# Sheet1.net
KiCad netlist of a schematic drawn in Altium Designer
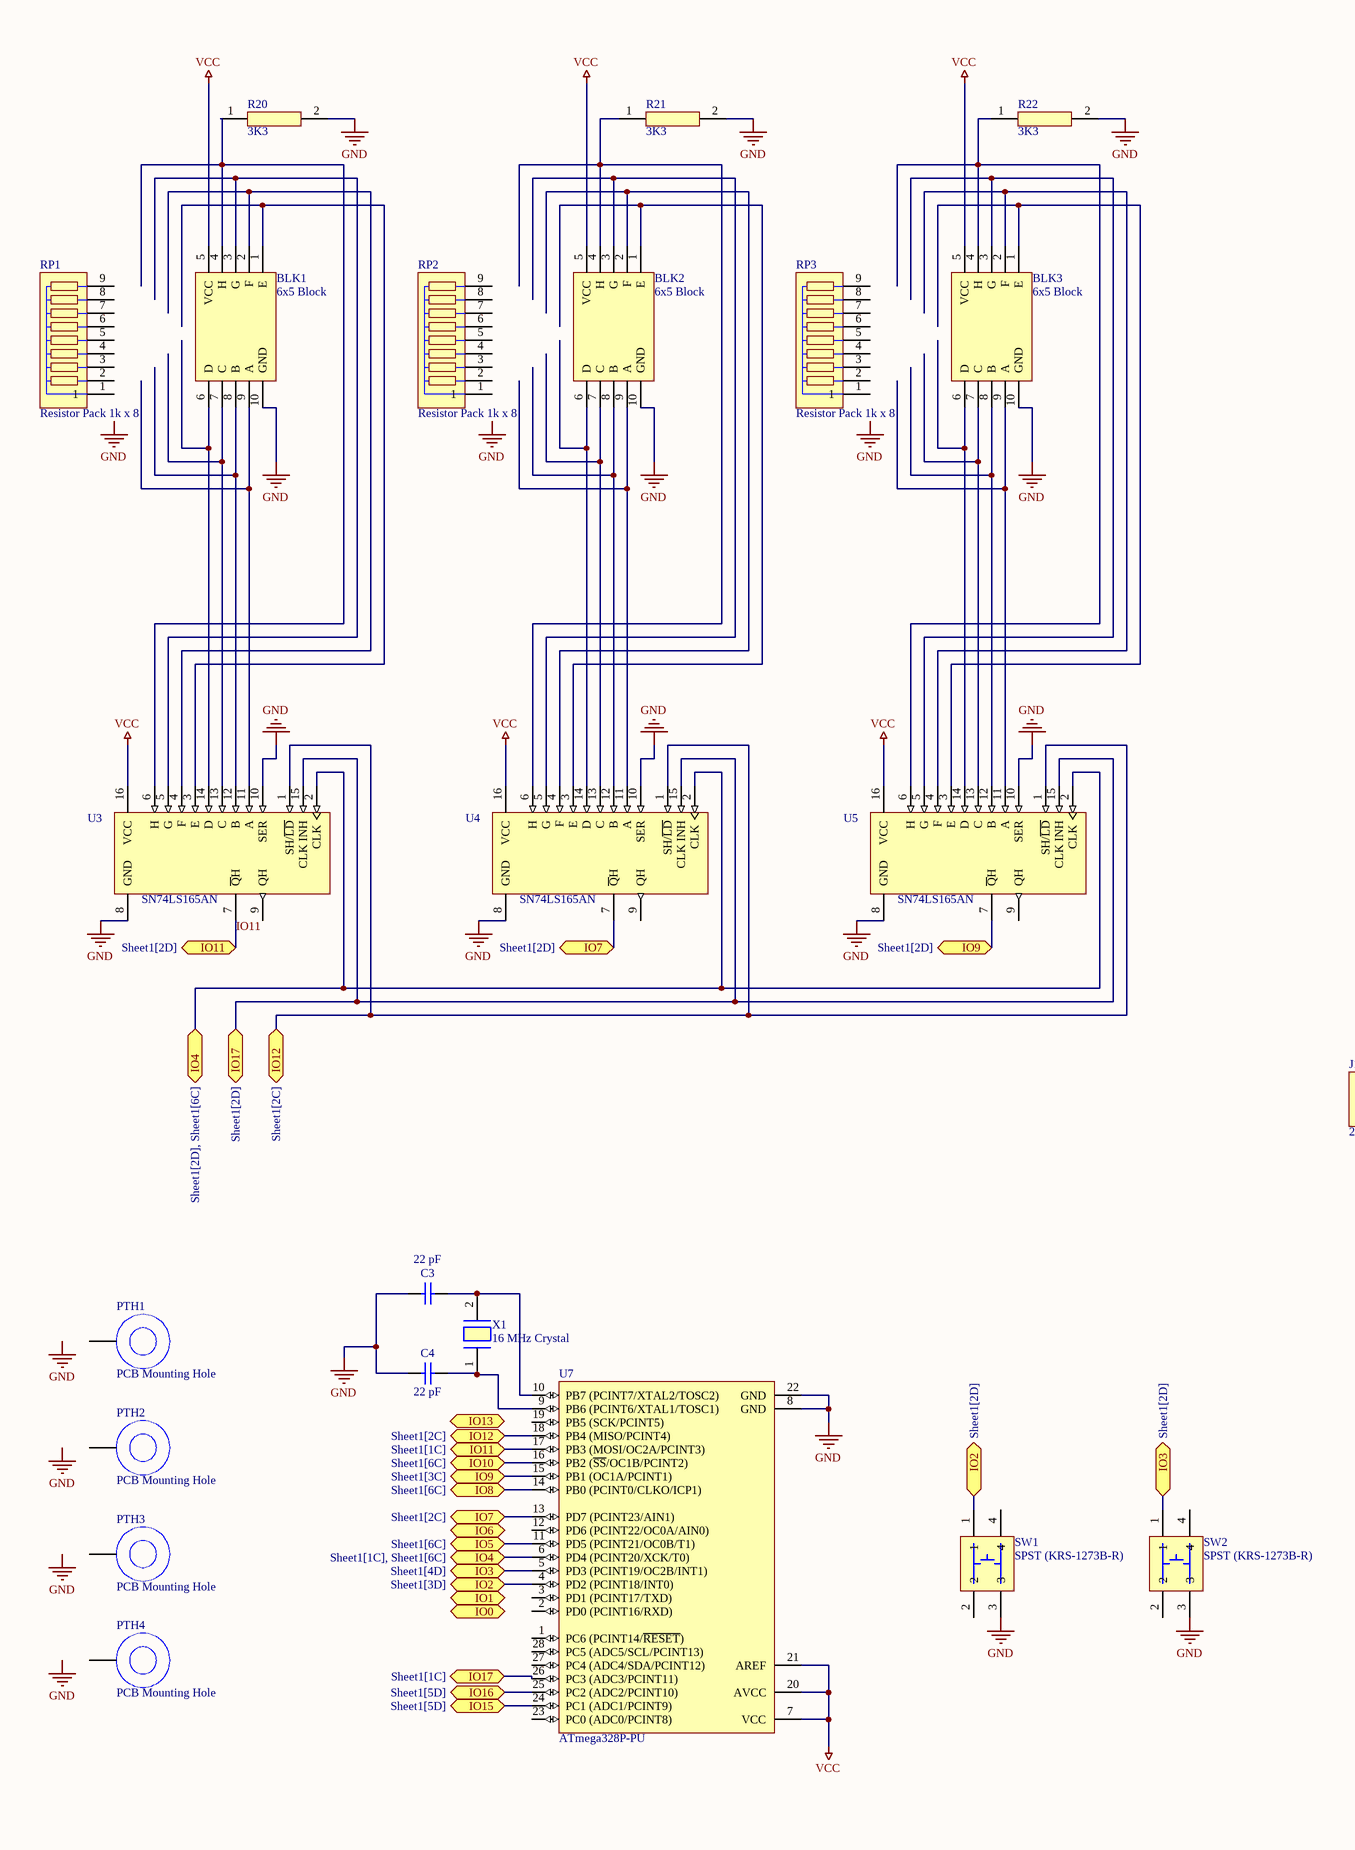
[diagram p0: Sheet1.SchDoc, left]
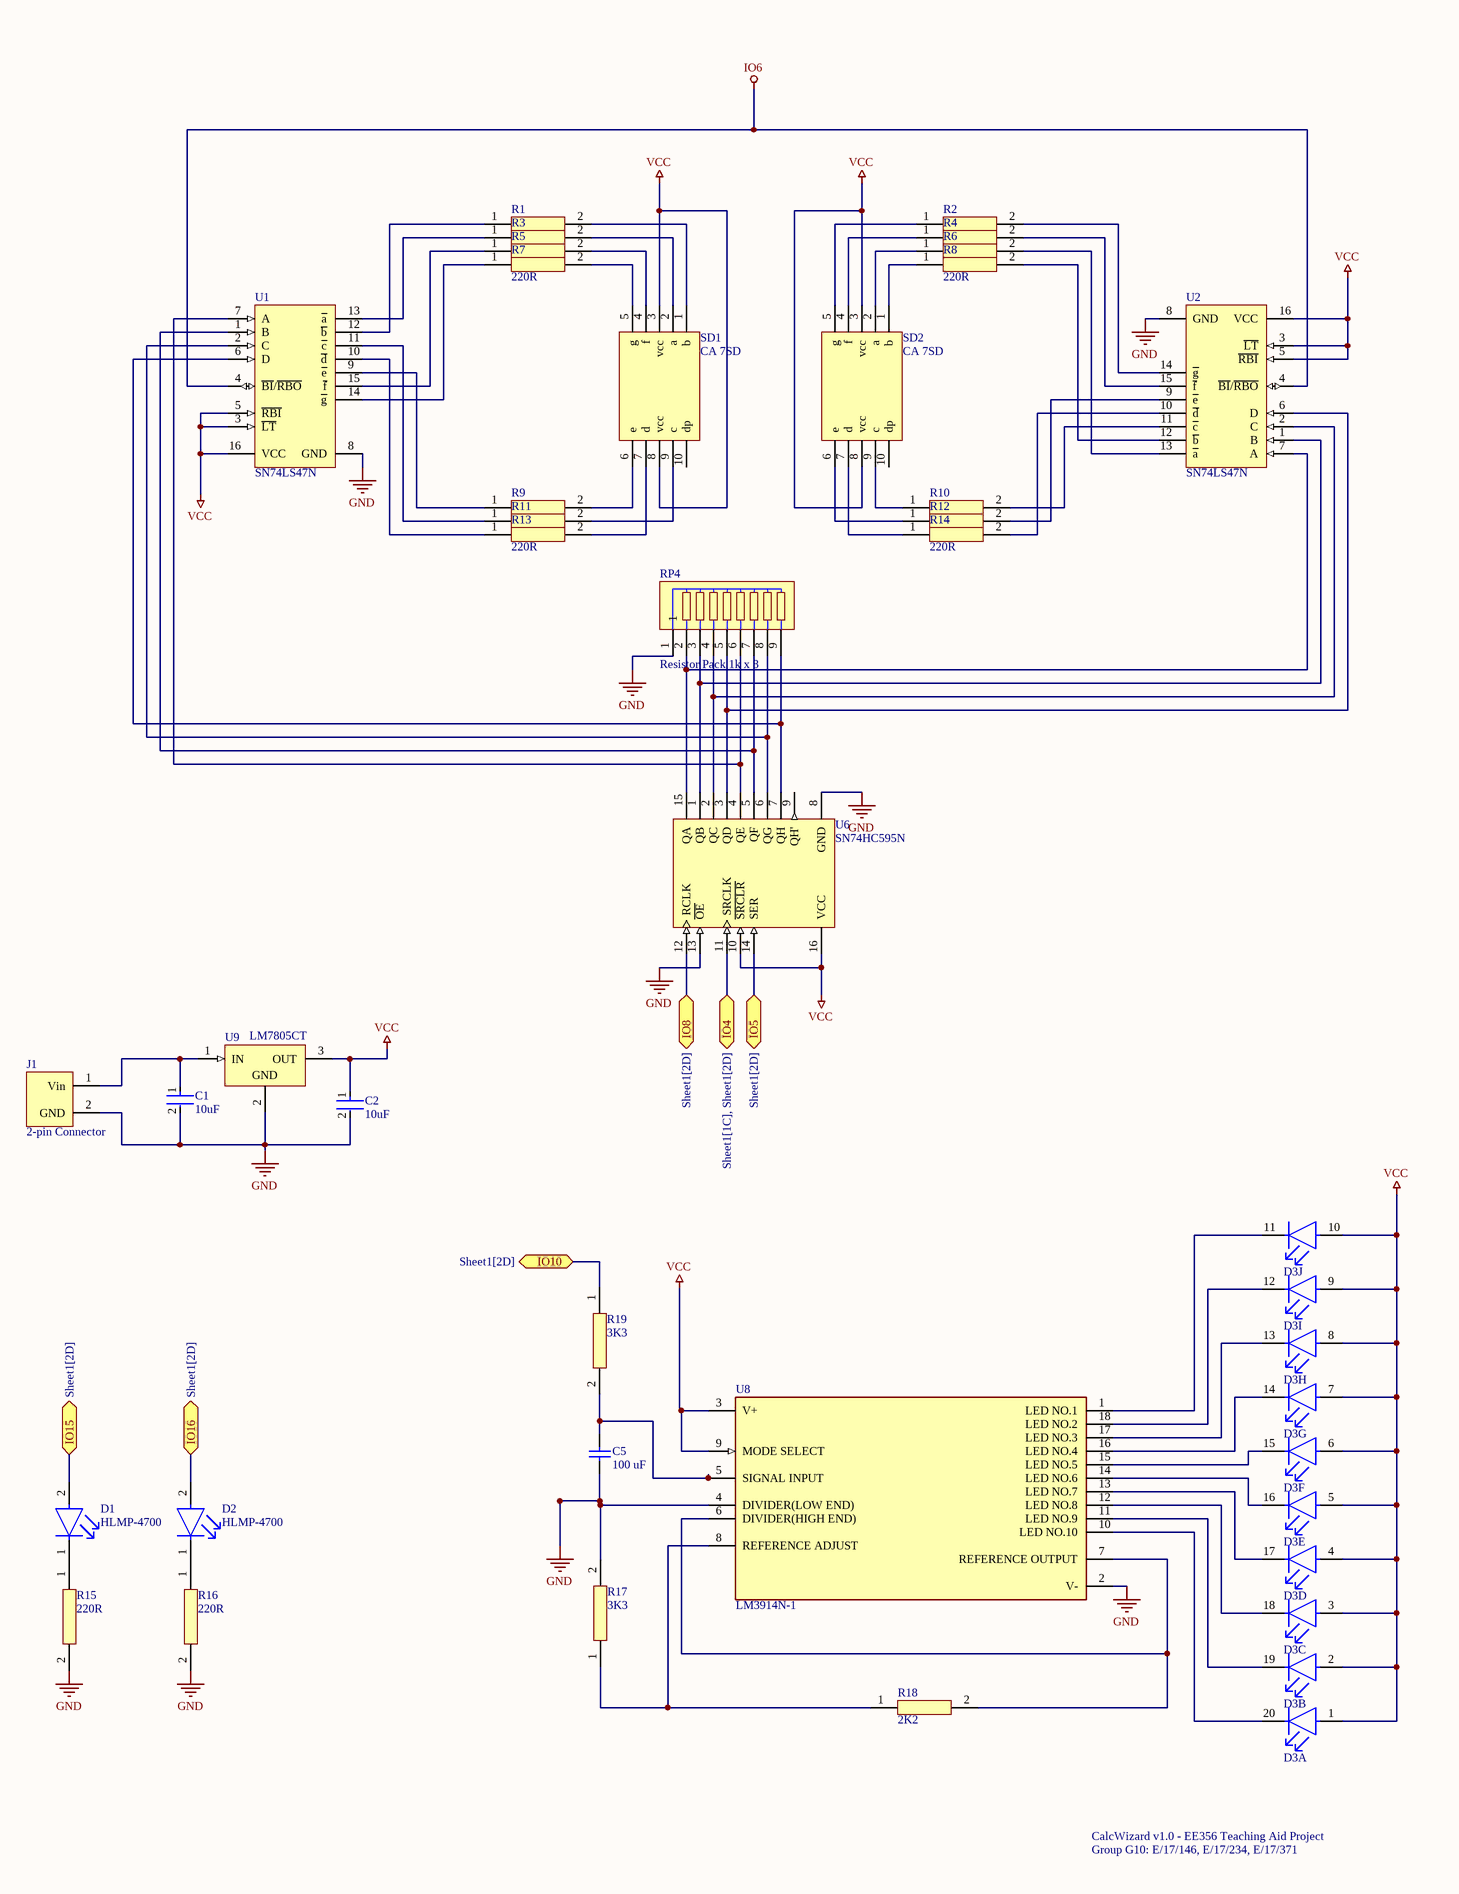
[diagram p1: Sheet1.SchDoc, right]

(export (version "E")
  (design (tool "Eeschema 10.0.6"))
  (components
    (comp (ref "BLK1")
      (value "6x5 Block")
      (footprint "Block_6x5")
      (libsource (lib "Schlib1") (part "Block_6x5"))
    )
    (comp (ref "BLK2")
      (value "6x5 Block")
      (footprint "Block_6x5")
      (libsource (lib "Schlib1") (part "Block_6x5"))
    )
    (comp (ref "BLK3")
      (value "6x5 Block")
      (footprint "Block_6x5")
      (libsource (lib "Schlib1") (part "Block_6x5"))
    )
    (comp (ref "C1")
      (value "10uF")
      (footprint "FP-RCE3DB-MFG")
      (description "Cap Ceramic 10uF 25V X7R ±10% Radial 2.5mm +125°C Automotive Bulk (RCER71E106K3A2H03B)")
      (fields (field (name "TOLERANCE") "10%"))
      (libsource (lib "Altium Content Vault") (part "b4654b650e69147ec39a6b967a45e02"))
    )
    (comp (ref "C2")
      (value "10uF")
      (footprint "FP-RCE3DB-MFG")
      (description "Cap Ceramic 10uF 25V X7R ±10% Radial 2.5mm +125°C Automotive Bulk (RCER71E106K3A2H03B)")
      (fields (field (name "TOLERANCE") "10%"))
      (libsource (lib "Altium Content Vault") (part "b4654b650e69147ec39a6b967a45e02"))
    )
    (comp (ref "C3")
      (value "22 pF")
      (footprint "KEMT-C315-THT-2")
      (description "Capacitor, Ceramic, 22 pF, +/-10 %, 100 V, -55 to 125 degC, 2-Pin THD, RoHS, Bulk")
      (libsource (lib "Altium Content Vault") (part "CAP-NP-2"))
    )
    (comp (ref "C4")
      (value "22 pF")
      (footprint "KEMT-C315-THT-2")
      (description "Capacitor, Ceramic, 22 pF, +/-10 %, 100 V, -55 to 125 degC, 2-Pin THD, RoHS, Bulk")
      (libsource (lib "Altium Content Vault") (part "CAP-NP-2"))
    )
    (comp (ref "C5")
      (value "100 uF")
      (footprint "KEMT-C315-THT-2")
      (description "Capacitor, Ceramic, 100 uF, +/-10 %, 100 V, -55 to 125 degC, 2-Pin THD, RoHS, Bulk")
      (libsource (lib "Altium Content Vault") (part "CAP-NP-2"))
    )
    (comp (ref "D1")
      (value "HLMP-4700")
      (footprint "FP-HLMP-4700-MFG")
      (description "LED RED DIFFUSED T-1 3/4 T/H")
      (fields
        (field (name "OCTOPART") "https://octopart.com/hlmp-4700-broadcom-71130526")
        (field (name "MANUFACTURER") "Broadcom")
      )
      (libsource (lib "Altium Content Vault") (part "8706943c75ba83719d021d2fdc84c58"))
    )
    (comp (ref "D2")
      (value "HLMP-4700")
      (footprint "FP-HLMP-4700-MFG")
      (description "LED RED DIFFUSED T-1 3/4 T/H")
      (fields
        (field (name "OCTOPART") "https://octopart.com/hlmp-4700-broadcom-71130526")
        (field (name "MANUFACTURER") "Broadcom")
      )
      (libsource (lib "Altium Content Vault") (part "8706943c75ba83719d021d2fdc84c58"))
    )
    (comp (ref "D3")
      (value "SSA-LXB10HW-GF/LP")
      (footprint "FP-SSA-LXB10HW-GF-LP-MFG")
      (description "LED ARRAY 10X25MM 10SEG RED DIFF")
      (fields
        (field (name "OCTOPART") "https://octopart.com/ssa-lxb10hw-gf%2Flp-lumex-548235")
        (field (name "MANUFACTURER") "lumex")
      )
      (libsource (lib "Altium Content Vault") (part "0ad3f8813297581e4dba16f0763b6c7"))
    )
    (comp (ref "J1")
      (value "2-pin Connector")
      (footprint "2-pin Connector")
      (description "Female, 2C, Straight, .100\"CC; 3.20mm Tail, No Mt. 100u\" Tin; PBT, Phos Bronze, 105 C")
      (fields
        (field (name "MANUFACTURER") "Sullins")
        (field (name "MANUFACTURER PART NUMBER") "PPTC021LFBN-RC")
      )
      (libsource (lib "Schlib1") (part "PPTC021LFBN-RC"))
    )
    (comp (ref "PTH1")
      (value "PCB Mounting Hole")
      (footprint "PTH 2mm")
      (libsource (lib "Schlib1") (part "PTH"))
    )
    (comp (ref "PTH2")
      (value "PCB Mounting Hole")
      (footprint "PTH 2mm")
      (libsource (lib "Schlib1") (part "PTH"))
    )
    (comp (ref "PTH3")
      (value "PCB Mounting Hole")
      (footprint "PTH 2mm")
      (libsource (lib "Schlib1") (part "PTH"))
    )
    (comp (ref "PTH4")
      (value "PCB Mounting Hole")
      (footprint "PTH 2mm")
      (libsource (lib "Schlib1") (part "PTH"))
    )
    (comp (ref "R1")
      (value "220R")
      (footprint "CFR_400mil")
      (description "General Type Carbon Film Resistor 220Ohm 1/4W 5% Axial Bulk")
      (fields
        (field (name "MANUFACTURER") "Yageo")
        (field (name "MANUFACTURER PART NUMBER") "CFR-25JB-52-220R")
      )
      (libsource (lib "Schlib1") (part "CFR-25JB-52-220R"))
    )
    (comp (ref "R2")
      (value "220R")
      (footprint "CFR_400mil")
      (description "General Type Carbon Film Resistor 220Ohm 1/4W 5% Axial Bulk")
      (fields
        (field (name "MANUFACTURER") "Yageo")
        (field (name "MANUFACTURER PART NUMBER") "CFR-25JB-52-220R")
      )
      (libsource (lib "Schlib1") (part "CFR-25JB-52-220R"))
    )
    (comp (ref "R3")
      (value "220R")
      (footprint "CFR_400mil")
      (description "General Type Carbon Film Resistor 220Ohm 1/4W 5% Axial Bulk")
      (fields
        (field (name "MANUFACTURER") "Yageo")
        (field (name "MANUFACTURER PART NUMBER") "CFR-25JB-52-220R")
      )
      (libsource (lib "Schlib1") (part "CFR-25JB-52-220R"))
    )
    (comp (ref "R4")
      (value "220R")
      (footprint "CFR_400mil")
      (description "General Type Carbon Film Resistor 220Ohm 1/4W 5% Axial Bulk")
      (fields
        (field (name "MANUFACTURER") "Yageo")
        (field (name "MANUFACTURER PART NUMBER") "CFR-25JB-52-220R")
      )
      (libsource (lib "Schlib1") (part "CFR-25JB-52-220R"))
    )
    (comp (ref "R5")
      (value "220R")
      (footprint "CFR_400mil")
      (description "General Type Carbon Film Resistor 220Ohm 1/4W 5% Axial Bulk")
      (fields
        (field (name "MANUFACTURER") "Yageo")
        (field (name "MANUFACTURER PART NUMBER") "CFR-25JB-52-220R")
      )
      (libsource (lib "Schlib1") (part "CFR-25JB-52-220R"))
    )
    (comp (ref "R6")
      (value "220R")
      (footprint "CFR_400mil")
      (description "General Type Carbon Film Resistor 220Ohm 1/4W 5% Axial Bulk")
      (fields
        (field (name "MANUFACTURER") "Yageo")
        (field (name "MANUFACTURER PART NUMBER") "CFR-25JB-52-220R")
      )
      (libsource (lib "Schlib1") (part "CFR-25JB-52-220R"))
    )
    (comp (ref "R7")
      (value "220R")
      (footprint "CFR_400mil")
      (description "General Type Carbon Film Resistor 220Ohm 1/4W 5% Axial Bulk")
      (fields
        (field (name "MANUFACTURER") "Yageo")
        (field (name "MANUFACTURER PART NUMBER") "CFR-25JB-52-220R")
      )
      (libsource (lib "Schlib1") (part "CFR-25JB-52-220R"))
    )
    (comp (ref "R8")
      (value "220R")
      (footprint "CFR_400mil")
      (description "General Type Carbon Film Resistor 220Ohm 1/4W 5% Axial Bulk")
      (fields
        (field (name "MANUFACTURER") "Yageo")
        (field (name "MANUFACTURER PART NUMBER") "CFR-25JB-52-220R")
      )
      (libsource (lib "Schlib1") (part "CFR-25JB-52-220R"))
    )
    (comp (ref "R9")
      (value "220R")
      (footprint "CFR_400mil")
      (description "General Type Carbon Film Resistor 220Ohm 1/4W 5% Axial Bulk")
      (fields
        (field (name "MANUFACTURER") "Yageo")
        (field (name "MANUFACTURER PART NUMBER") "CFR-25JB-52-220R")
      )
      (libsource (lib "Schlib1") (part "CFR-25JB-52-220R"))
    )
    (comp (ref "R10")
      (value "220R")
      (footprint "CFR_400mil")
      (description "General Type Carbon Film Resistor 220Ohm 1/4W 5% Axial Bulk")
      (fields
        (field (name "MANUFACTURER") "Yageo")
        (field (name "MANUFACTURER PART NUMBER") "CFR-25JB-52-220R")
      )
      (libsource (lib "Schlib1") (part "CFR-25JB-52-220R"))
    )
    (comp (ref "R11")
      (value "220R")
      (footprint "CFR_400mil")
      (description "General Type Carbon Film Resistor 220Ohm 1/4W 5% Axial Bulk")
      (fields
        (field (name "MANUFACTURER") "Yageo")
        (field (name "MANUFACTURER PART NUMBER") "CFR-25JB-52-220R")
      )
      (libsource (lib "Schlib1") (part "CFR-25JB-52-220R"))
    )
    (comp (ref "R12")
      (value "220R")
      (footprint "CFR_400mil")
      (description "General Type Carbon Film Resistor 220Ohm 1/4W 5% Axial Bulk")
      (fields
        (field (name "MANUFACTURER") "Yageo")
        (field (name "MANUFACTURER PART NUMBER") "CFR-25JB-52-220R")
      )
      (libsource (lib "Schlib1") (part "CFR-25JB-52-220R"))
    )
    (comp (ref "R13")
      (value "220R")
      (footprint "CFR_400mil")
      (description "General Type Carbon Film Resistor 220Ohm 1/4W 5% Axial Bulk")
      (fields
        (field (name "MANUFACTURER") "Yageo")
        (field (name "MANUFACTURER PART NUMBER") "CFR-25JB-52-220R")
      )
      (libsource (lib "Schlib1") (part "CFR-25JB-52-220R"))
    )
    (comp (ref "R14")
      (value "220R")
      (footprint "CFR_400mil")
      (description "General Type Carbon Film Resistor 220Ohm 1/4W 5% Axial Bulk")
      (fields
        (field (name "MANUFACTURER") "Yageo")
        (field (name "MANUFACTURER PART NUMBER") "CFR-25JB-52-220R")
      )
      (libsource (lib "Schlib1") (part "CFR-25JB-52-220R"))
    )
    (comp (ref "R15")
      (value "220R")
      (footprint "CFR_400mil")
      (description "General Type Carbon Film Resistor 220Ohm 1/4W 5% Axial Bulk")
      (fields
        (field (name "MANUFACTURER") "Yageo")
        (field (name "MANUFACTURER PART NUMBER") "CFR-25JB-52-220R")
      )
      (libsource (lib "") (part "CFR-25JB-52-220R_1"))
    )
    (comp (ref "R16")
      (value "220R")
      (footprint "CFR_400mil")
      (description "General Type Carbon Film Resistor 220Ohm 1/4W 5% Axial Bulk")
      (fields
        (field (name "MANUFACTURER") "Yageo")
        (field (name "MANUFACTURER PART NUMBER") "CFR-25JB-52-220R")
      )
      (libsource (lib "") (part "CFR-25JB-52-220R_1"))
    )
    (comp (ref "R17")
      (value "3K3")
      (footprint "CFR_400mil")
      (description "General Type Carbon Film Resistor 3.3kOhm 1/4W 5% Axial Bulk")
      (fields
        (field (name "MANUFACTURER") "Yageo")
        (field (name "MANUFACTURER PART NUMBER") "CFR-25JB-52-220R")
      )
      (libsource (lib "") (part "CFR-25JB-52-3K3_1"))
    )
    (comp (ref "R18")
      (value "2K2")
      (footprint "CFR_400mil")
      (description "General Type Carbon Film Resistor 2.2kOhm 1/4W 5% Axial Bulk")
      (fields
        (field (name "MANUFACTURER") "Yageo")
        (field (name "MANUFACTURER PART NUMBER") "CFR-25JB-52-220R")
      )
      (libsource (lib "Schlib1") (part "CFR-25JB-52-2K2"))
    )
    (comp (ref "R19")
      (value "3K3")
      (footprint "CFR_400mil")
      (description "General Type Carbon Film Resistor 3.3kOhm 1/4W 5% Axial Bulk")
      (fields
        (field (name "MANUFACTURER") "Yageo")
        (field (name "MANUFACTURER PART NUMBER") "CFR-25JB-52-220R")
      )
      (libsource (lib "") (part "CFR-25JB-52-3K3_2"))
    )
    (comp (ref "R20")
      (value "3K3")
      (footprint "CFR_400mil")
      (description "General Type Carbon Film Resistor 3.3kOhm 1/4W 5% Axial Bulk")
      (fields
        (field (name "MANUFACTURER") "Yageo")
        (field (name "MANUFACTURER PART NUMBER") "CFR-25JB-52-220R")
      )
      (libsource (lib "Schlib1") (part "CFR-25JB-52-3K3"))
    )
    (comp (ref "R21")
      (value "3K3")
      (footprint "CFR_400mil")
      (description "General Type Carbon Film Resistor 3.3kOhm 1/4W 5% Axial Bulk")
      (fields
        (field (name "MANUFACTURER") "Yageo")
        (field (name "MANUFACTURER PART NUMBER") "CFR-25JB-52-220R")
      )
      (libsource (lib "Schlib1") (part "CFR-25JB-52-3K3"))
    )
    (comp (ref "R22")
      (value "3K3")
      (footprint "CFR_400mil")
      (description "General Type Carbon Film Resistor 3.3kOhm 1/4W 5% Axial Bulk")
      (fields
        (field (name "MANUFACTURER") "Yageo")
        (field (name "MANUFACTURER PART NUMBER") "CFR-25JB-52-220R")
      )
      (libsource (lib "Schlib1") (part "CFR-25JB-52-3K3"))
    )
    (comp (ref "RP1")
      (value "Resistor Pack 1k x 8")
      (footprint "Resistor Pack 1k x 8")
      (description "Res Thick Film NET 1K Ohm 2% 1.13W ±100ppm/°C BUS Molded 9-Pin SIP Pin Thru-Hole")
      (fields
        (field (name "MANUFACTURER") "Bourns")
        (field (name "MANUFACTURER PART NUMBER") "4309R-101-102LF")
      )
      (libsource (lib "") (part "4309R-101-102LF_1"))
    )
    (comp (ref "RP2")
      (value "Resistor Pack 1k x 8")
      (footprint "Resistor Pack 1k x 8")
      (description "Res Thick Film NET 1K Ohm 2% 1.13W ±100ppm/°C BUS Molded 9-Pin SIP Pin Thru-Hole")
      (fields
        (field (name "MANUFACTURER") "Bourns")
        (field (name "MANUFACTURER PART NUMBER") "4309R-101-102LF")
      )
      (libsource (lib "") (part "4309R-101-102LF_1"))
    )
    (comp (ref "RP3")
      (value "Resistor Pack 1k x 8")
      (footprint "Resistor Pack 1k x 8")
      (description "Res Thick Film NET 1K Ohm 2% 1.13W ±100ppm/°C BUS Molded 9-Pin SIP Pin Thru-Hole")
      (fields
        (field (name "MANUFACTURER") "Bourns")
        (field (name "MANUFACTURER PART NUMBER") "4309R-101-102LF")
      )
      (libsource (lib "") (part "4309R-101-102LF_1"))
    )
    (comp (ref "RP4")
      (value "Resistor Pack 1k x 8")
      (footprint "Resistor Pack 1k x 8")
      (description "Res Thick Film NET 1K Ohm 2% 1.13W ±100ppm/°C BUS Molded 9-Pin SIP Pin Thru-Hole")
      (fields
        (field (name "MANUFACTURER") "Bourns")
        (field (name "MANUFACTURER PART NUMBER") "4309R-101-102LF")
      )
      (libsource (lib "Schlib1") (part "4309R-101-102LF"))
    )
    (comp (ref "SD1")
      (value "CA 7SD")
      (footprint "CA 7SD")
      (description "Single Digit Seven Segment Green 0.56\" Common Anode Through Hole LED Display")
      (fields (field (name "MANUFACTURER") "Lumex") (field (name "MANUFACTURER PART NUMBER") "LDS-A5642RI"))
      (libsource (lib "Schlib1") (part "LDS-A5642RI"))
    )
    (comp (ref "SD2")
      (value "CA 7SD")
      (footprint "CA 7SD")
      (description "Single Digit Seven Segment Green 0.56\" Common Anode Through Hole LED Display")
      (fields (field (name "MANUFACTURER") "Lumex") (field (name "MANUFACTURER PART NUMBER") "LDS-A5642RI"))
      (libsource (lib "Schlib1") (part "LDS-A5642RI"))
    )
    (comp (ref "SW1")
      (value "SPST (KRS-1273B-R)")
      (footprint "SPST KRS-1273B-R")
      (description "Switch Push Button Tactile Off Momentary (On) Single Pole Single Throw Cap: 155389 155409")
      (fields
        (field (name "MANUFACTURER") "Jameco Valuepro")
        (field (name "MANUFACTURER PART NUMBER") "KRS-1273B-R")
      )
      (libsource (lib "Schlib1") (part "KRS-1273B-R"))
    )
    (comp (ref "SW2")
      (value "SPST (KRS-1273B-R)")
      (footprint "SPST KRS-1273B-R")
      (description "Switch Push Button Tactile Off Momentary (On) Single Pole Single Throw Cap: 155389 155409")
      (fields
        (field (name "MANUFACTURER") "Jameco Valuepro")
        (field (name "MANUFACTURER PART NUMBER") "KRS-1273B-R")
      )
      (libsource (lib "Schlib1") (part "KRS-1273B-R"))
    )
    (comp (ref "U1")
      (value "SN74LS47N")
      (footprint "N0016A")
      (description "BCD-to-7-Segment Decoder / Driver, 4.75 to 5.25 V, 0 to 70 degC, 16-pin DIP (N16), Pb-Free (RoHS)")
      (fields (field (name "MANUFACTURER") "Texas Instruments"))
      (libsource (lib "Altium Content Vault") (part "TI-SNX4XX247-16"))
    )
    (comp (ref "U2")
      (value "SN74LS47N")
      (footprint "N0016A")
      (description "BCD-to-7-Segment Decoder / Driver, 4.75 to 5.25 V, 0 to 70 degC, 16-pin DIP (N16), Pb-Free (RoHS)")
      (fields (field (name "MANUFACTURER") "Texas Instruments"))
      (libsource (lib "") (part "TI-SNX4XX247-16_1"))
    )
    (comp (ref "U3")
      (value "SN74LS165AN")
      (footprint "N0016A")
      (description "Serial-out shift registers, N0016A, TUBE")
      (fields
        (field (name "GENERIC PART NUMBER") "SN74LS165A")
        (field (name "MANUFACTURER") "Texas Instruments")
      )
      (libsource (lib "Altium Content Vault") (part "TI-SNX4XXX165X-16"))
    )
    (comp (ref "U4")
      (value "SN74LS165AN")
      (footprint "N0016A")
      (description "Serial-out shift registers, N0016A, TUBE")
      (fields
        (field (name "GENERIC PART NUMBER") "SN74LS165A")
        (field (name "MANUFACTURER") "Texas Instruments")
      )
      (libsource (lib "Altium Content Vault") (part "TI-SNX4XXX165X-16"))
    )
    (comp (ref "U5")
      (value "SN74LS165AN")
      (footprint "N0016A")
      (description "Serial-out shift registers, N0016A, TUBE")
      (fields
        (field (name "GENERIC PART NUMBER") "SN74LS165A")
        (field (name "MANUFACTURER") "Texas Instruments")
      )
      (libsource (lib "Altium Content Vault") (part "TI-SNX4XXX165X-16"))
    )
    (comp (ref "U6")
      (value "SN74HC595N")
      (footprint "N0016A")
      (description "8-Bit Shift Registers With 3-State Output Registers, N0016A, TUBE")
      (fields
        (field (name "GENERIC PART NUMBER") "SN74HC595")
        (field (name "MANUFACTURER") "Texas Instruments")
      )
      (libsource (lib "Altium Content Vault") (part "TI-SN74XHCT595X_SN74LV595A-16"))
    )
    (comp (ref "U7")
      (value "ATmega328P-PU")
      (footprint "28P3")
      (libsource (lib "Altium Content Vault") (part "MC-8B-ATM48-IL28"))
    )
    (comp (ref "U8")
      (value "LM3914N-1")
      (footprint "FP-NFK0018A-MFG")
      (description "IC DRVR DOT/BAR DISPLAY 18DIP")
      (libsource (lib "Altium Content Vault") (part "8d9105b9cf50def005be23956edfdd2"))
    )
    (comp (ref "U9")
      (value "LM7805CT")
      (footprint "FAIR-TO-220-3")
      (description "Positive Voltage Regulator, 5 V, 1 A, -40 to 125 degC, 3-Pin TO-220, RoHS, Tube")
      (fields (field (name "MANUFACTURER") "FairchildSemiconductor"))
      (libsource (lib "Altium Content Vault") (part "FAIR-LM7805CT-TO220-3"))
    )
    (comp (ref "X1")
      (value "16 MHz Crystal")
      (footprint "Crystal Osc TH")
      (description "Crystal 16MHz ±50ppm (Tol) ±50ppm (Stability) 20pF FUND 30Ohm 2-Pin DIP HC-49/S Thru-Hole Bulk")
      (fields (field (name "MANUFACTURER") "TXC") (field (name "MANUFACTURER PART NUMBER") "9B-16.000MBBK-B"))
      (libsource (lib "Schlib1") (part "9B-16.000MBBK-B"))
    )
  )
  (nets
    (net (code "3") (name "/IO2") (class "Default")
      (node (ref "SW1") (pin "1") (pinfunction "1_1") (pintype "passive"))
      (node (ref "U7") (pin "4") (pinfunction "PD2_(PCINT18/INT0)_4") (pintype "bidirectional"))
    )
    (net (code "4") (name "/IO3") (class "Default")
      (node (ref "SW2") (pin "1") (pinfunction "1_1") (pintype "passive"))
      (node (ref "U7") (pin "5") (pinfunction "PD3_(PCINT19/OC2B/INT1)_5") (pintype "bidirectional"))
    )
    (net (code "5") (name "/IO4") (class "Default")
      (node (ref "U3") (pin "2") (pinfunction "CLK_2") (pintype "input"))
      (node (ref "U4") (pin "2") (pinfunction "CLK_2") (pintype "input"))
      (node (ref "U5") (pin "2") (pinfunction "CLK_2") (pintype "input"))
      (node (ref "U6") (pin "11") (pinfunction "SRCLK_11") (pintype "input"))
      (node (ref "U7") (pin "6") (pinfunction "PD4_(PCINT20/XCK/T0)_6") (pintype "bidirectional"))
    )
    (net (code "6") (name "/IO5") (class "Default")
      (node (ref "U6") (pin "14") (pinfunction "SER_14") (pintype "input"))
      (node (ref "U7") (pin "11") (pinfunction "PD5_(PCINT21/OC0B/T1)_11") (pintype "bidirectional"))
    )
    (net (code "7") (name "/IO7") (class "Default")
      (node (ref "U4") (pin "7") (pinfunction "~{Q}H_7") (pintype "passive"))
      (node (ref "U7") (pin "13") (pinfunction "PD7_(PCINT23/AIN1)_13") (pintype "bidirectional"))
    )
    (net (code "8") (name "/IO8") (class "Default")
      (node (ref "U6") (pin "12") (pinfunction "RCLK_12") (pintype "input"))
      (node (ref "U7") (pin "14") (pinfunction "PB0_(PCINT0/CLKO/ICP1)_14") (pintype "bidirectional"))
    )
    (net (code "9") (name "/IO9") (class "Default")
      (node (ref "U5") (pin "7") (pinfunction "~{Q}H_7") (pintype "passive"))
      (node (ref "U7") (pin "15") (pinfunction "PB1_(OC1A/PCINT1)_15") (pintype "bidirectional"))
    )
    (net (code "10") (name "/IO10") (class "Default")
      (node (ref "R19") (pin "1") (pinfunction "1_1") (pintype "passive"))
      (node (ref "U7") (pin "16") (pinfunction "PB2_(~{SS}/OC1B/PCINT2)_16") (pintype "bidirectional"))
    )
    (net (code "11") (name "/IO11") (class "Default")
      (node (ref "U3") (pin "7") (pinfunction "~{Q}H_7") (pintype "passive"))
      (node (ref "U7") (pin "17") (pinfunction "PB3_(MOSI/OC2A/PCINT3)_17") (pintype "bidirectional"))
    )
    (net (code "12") (name "/IO12") (class "Default")
      (node (ref "U3") (pin "1") (pinfunction "SH/~{LD}_1") (pintype "input"))
      (node (ref "U4") (pin "1") (pinfunction "SH/~{LD}_1") (pintype "input"))
      (node (ref "U5") (pin "1") (pinfunction "SH/~{LD}_1") (pintype "input"))
      (node (ref "U7") (pin "18") (pinfunction "PB4_(MISO/PCINT4)_18") (pintype "bidirectional"))
    )
    (net (code "14") (name "/IO15") (class "Default")
      (node (ref "D1") (pin "2") (pinfunction "A_2") (pintype "passive"))
      (node (ref "U7") (pin "24") (pinfunction "PC1_(ADC1/PCINT9)_24") (pintype "bidirectional"))
    )
    (net (code "15") (name "/IO16") (class "Default")
      (node (ref "D2") (pin "2") (pinfunction "A_2") (pintype "passive"))
      (node (ref "U7") (pin "25") (pinfunction "PC2_(ADC2/PCINT10)_25") (pintype "bidirectional"))
    )
    (net (code "16") (name "/IO17") (class "Default")
      (node (ref "U3") (pin "15") (pinfunction "CLK_INH_15") (pintype "input"))
      (node (ref "U4") (pin "15") (pinfunction "CLK_INH_15") (pintype "input"))
      (node (ref "U5") (pin "15") (pinfunction "CLK_INH_15") (pintype "input"))
      (node (ref "U7") (pin "26") (pinfunction "PC3_(ADC3/PCINT11)_26") (pintype "bidirectional"))
    )
    (net (code "17") (name "GND") (class "Default")
      (node (ref "BLK1") (pin "10") (pinfunction "GND_10") (pintype "passive"))
      (node (ref "BLK2") (pin "10") (pinfunction "GND_10") (pintype "passive"))
      (node (ref "BLK3") (pin "10") (pinfunction "GND_10") (pintype "passive"))
      (node (ref "C1") (pin "2") (pinfunction "2_2") (pintype "passive"))
      (node (ref "C2") (pin "2") (pinfunction "2_2") (pintype "passive"))
      (node (ref "C3") (pin "1") (pinfunction "1_1") (pintype "passive"))
      (node (ref "C4") (pin "1") (pinfunction "1_1") (pintype "passive"))
      (node (ref "C5") (pin "1") (pinfunction "1_1") (pintype "passive"))
      (node (ref "J1") (pin "2") (pinfunction "GND_2") (pintype "passive"))
      (node (ref "R15") (pin "2") (pinfunction "2_2") (pintype "passive"))
      (node (ref "R16") (pin "2") (pinfunction "2_2") (pintype "passive"))
      (node (ref "R17") (pin "2") (pinfunction "2_2") (pintype "passive"))
      (node (ref "R20") (pin "2") (pinfunction "2_2") (pintype "passive"))
      (node (ref "R21") (pin "2") (pinfunction "2_2") (pintype "passive"))
      (node (ref "R22") (pin "2") (pinfunction "2_2") (pintype "passive"))
      (node (ref "RP4") (pin "1") (pinfunction "1_1") (pintype "passive"))
      (node (ref "SW1") (pin "3") (pinfunction "3_3") (pintype "passive"))
      (node (ref "SW2") (pin "3") (pinfunction "3_3") (pintype "passive"))
      (node (ref "U1") (pin "8") (pinfunction "GND_8") (pintype "power_in"))
      (node (ref "U2") (pin "8") (pinfunction "GND_8") (pintype "power_in"))
      (node (ref "U3") (pin "10") (pinfunction "SER_10") (pintype "input"))
      (node (ref "U3") (pin "8") (pinfunction "GND_8") (pintype "power_in"))
      (node (ref "U4") (pin "10") (pinfunction "SER_10") (pintype "input"))
      (node (ref "U4") (pin "8") (pinfunction "GND_8") (pintype "power_in"))
      (node (ref "U5") (pin "10") (pinfunction "SER_10") (pintype "input"))
      (node (ref "U5") (pin "8") (pinfunction "GND_8") (pintype "power_in"))
      (node (ref "U6") (pin "13") (pinfunction "~{OE}_13") (pintype "input"))
      (node (ref "U6") (pin "8") (pinfunction "GND_8") (pintype "power_in"))
      (node (ref "U7") (pin "22") (pinfunction "GND_22") (pintype "power_in"))
      (node (ref "U7") (pin "8") (pinfunction "GND_8") (pintype "power_in"))
      (node (ref "U8") (pin "2") (pinfunction "V-_2") (pintype "power_in"))
      (node (ref "U8") (pin "4") (pinfunction "DIVIDER(LOW_END)_4") (pintype "passive"))
      (node (ref "U9") (pin "2") (pinfunction "GND_2") (pintype "power_in"))
    )
    (net (code "18") (name "IO6") (class "Default")
      (node (ref "U1") (pin "4") (pinfunction "~{BI}/~{RBO}_4") (pintype "bidirectional"))
      (node (ref "U2") (pin "4") (pinfunction "~{BI}/~{RBO}_4") (pintype "bidirectional"))
    )
    (net (code "19") (name "Net-(BLK1-A)") (class "Default")
      (node (ref "BLK1") (pin "9") (pinfunction "A_9") (pintype "passive"))
      (node (ref "U3") (pin "11") (pinfunction "A_11") (pintype "input"))
    )
    (net (code "20") (name "Net-(BLK1-B)") (class "Default")
      (node (ref "BLK1") (pin "8") (pinfunction "B_8") (pintype "passive"))
      (node (ref "U3") (pin "12") (pinfunction "B_12") (pintype "input"))
    )
    (net (code "21") (name "Net-(BLK1-C)") (class "Default")
      (node (ref "BLK1") (pin "7") (pinfunction "C_7") (pintype "passive"))
      (node (ref "U3") (pin "13") (pinfunction "C_13") (pintype "input"))
    )
    (net (code "22") (name "Net-(BLK1-D)") (class "Default")
      (node (ref "BLK1") (pin "6") (pinfunction "D_6") (pintype "passive"))
      (node (ref "U3") (pin "14") (pinfunction "D_14") (pintype "input"))
    )
    (net (code "23") (name "Net-(BLK1-E)") (class "Default")
      (node (ref "BLK1") (pin "1") (pinfunction "E_1") (pintype "passive"))
      (node (ref "U3") (pin "3") (pinfunction "E_3") (pintype "input"))
    )
    (net (code "24") (name "Net-(BLK1-F)") (class "Default")
      (node (ref "BLK1") (pin "2") (pinfunction "F_2") (pintype "passive"))
      (node (ref "U3") (pin "4") (pinfunction "F_4") (pintype "input"))
    )
    (net (code "25") (name "Net-(BLK1-G)") (class "Default")
      (node (ref "BLK1") (pin "3") (pinfunction "G_3") (pintype "passive"))
      (node (ref "U3") (pin "5") (pinfunction "G_5") (pintype "input"))
    )
    (net (code "26") (name "Net-(BLK1-H)") (class "Default")
      (node (ref "BLK1") (pin "4") (pinfunction "H_4") (pintype "passive"))
      (node (ref "R20") (pin "1") (pinfunction "1_1") (pintype "passive"))
      (node (ref "U3") (pin "6") (pinfunction "H_6") (pintype "input"))
    )
    (net (code "27") (name "Net-(BLK2-A)") (class "Default")
      (node (ref "BLK2") (pin "9") (pinfunction "A_9") (pintype "passive"))
      (node (ref "U4") (pin "11") (pinfunction "A_11") (pintype "input"))
    )
    (net (code "28") (name "Net-(BLK2-B)") (class "Default")
      (node (ref "BLK2") (pin "8") (pinfunction "B_8") (pintype "passive"))
      (node (ref "U4") (pin "12") (pinfunction "B_12") (pintype "input"))
    )
    (net (code "29") (name "Net-(BLK2-C)") (class "Default")
      (node (ref "BLK2") (pin "7") (pinfunction "C_7") (pintype "passive"))
      (node (ref "U4") (pin "13") (pinfunction "C_13") (pintype "input"))
    )
    (net (code "30") (name "Net-(BLK2-D)") (class "Default")
      (node (ref "BLK2") (pin "6") (pinfunction "D_6") (pintype "passive"))
      (node (ref "U4") (pin "14") (pinfunction "D_14") (pintype "input"))
    )
    (net (code "31") (name "Net-(BLK2-E)") (class "Default")
      (node (ref "BLK2") (pin "1") (pinfunction "E_1") (pintype "passive"))
      (node (ref "U4") (pin "3") (pinfunction "E_3") (pintype "input"))
    )
    (net (code "32") (name "Net-(BLK2-F)") (class "Default")
      (node (ref "BLK2") (pin "2") (pinfunction "F_2") (pintype "passive"))
      (node (ref "U4") (pin "4") (pinfunction "F_4") (pintype "input"))
    )
    (net (code "33") (name "Net-(BLK2-G)") (class "Default")
      (node (ref "BLK2") (pin "3") (pinfunction "G_3") (pintype "passive"))
      (node (ref "U4") (pin "5") (pinfunction "G_5") (pintype "input"))
    )
    (net (code "34") (name "Net-(BLK2-H)") (class "Default")
      (node (ref "BLK2") (pin "4") (pinfunction "H_4") (pintype "passive"))
      (node (ref "R21") (pin "1") (pinfunction "1_1") (pintype "passive"))
      (node (ref "U4") (pin "6") (pinfunction "H_6") (pintype "input"))
    )
    (net (code "35") (name "Net-(BLK3-A)") (class "Default")
      (node (ref "BLK3") (pin "9") (pinfunction "A_9") (pintype "passive"))
      (node (ref "U5") (pin "11") (pinfunction "A_11") (pintype "input"))
    )
    (net (code "36") (name "Net-(BLK3-B)") (class "Default")
      (node (ref "BLK3") (pin "8") (pinfunction "B_8") (pintype "passive"))
      (node (ref "U5") (pin "12") (pinfunction "B_12") (pintype "input"))
    )
    (net (code "37") (name "Net-(BLK3-C)") (class "Default")
      (node (ref "BLK3") (pin "7") (pinfunction "C_7") (pintype "passive"))
      (node (ref "U5") (pin "13") (pinfunction "C_13") (pintype "input"))
    )
    (net (code "38") (name "Net-(BLK3-D)") (class "Default")
      (node (ref "BLK3") (pin "6") (pinfunction "D_6") (pintype "passive"))
      (node (ref "U5") (pin "14") (pinfunction "D_14") (pintype "input"))
    )
    (net (code "39") (name "Net-(BLK3-E)") (class "Default")
      (node (ref "BLK3") (pin "1") (pinfunction "E_1") (pintype "passive"))
      (node (ref "U5") (pin "3") (pinfunction "E_3") (pintype "input"))
    )
    (net (code "40") (name "Net-(BLK3-F)") (class "Default")
      (node (ref "BLK3") (pin "2") (pinfunction "F_2") (pintype "passive"))
      (node (ref "U5") (pin "4") (pinfunction "F_4") (pintype "input"))
    )
    (net (code "41") (name "Net-(BLK3-G)") (class "Default")
      (node (ref "BLK3") (pin "3") (pinfunction "G_3") (pintype "passive"))
      (node (ref "U5") (pin "5") (pinfunction "G_5") (pintype "input"))
    )
    (net (code "42") (name "Net-(BLK3-H)") (class "Default")
      (node (ref "BLK3") (pin "4") (pinfunction "H_4") (pintype "passive"))
      (node (ref "R22") (pin "1") (pinfunction "1_1") (pintype "passive"))
      (node (ref "U5") (pin "6") (pinfunction "H_6") (pintype "input"))
    )
    (net (code "43") (name "Net-(D1-C)") (class "Default")
      (node (ref "D1") (pin "1") (pinfunction "C_1") (pintype "passive"))
      (node (ref "R15") (pin "1") (pinfunction "1_1") (pintype "passive"))
    )
    (net (code "44") (name "Net-(D2-C)") (class "Default")
      (node (ref "D2") (pin "1") (pinfunction "C_1") (pintype "passive"))
      (node (ref "R16") (pin "1") (pinfunction "1_1") (pintype "passive"))
    )
    (net (code "45") (name "Net-(D3A-1_CATHODE)") (class "Default")
      (node (ref "D3") (pin "20") (pinfunction "1_CATHODE_20") (pintype "passive"))
      (node (ref "U8") (pin "10") (pinfunction "LED_NO.10_10") (pintype "passive"))
    )
    (net (code "46") (name "Net-(D3B-2_CATHODE)") (class "Default")
      (node (ref "D3") (pin "19") (pinfunction "2_CATHODE_19") (pintype "passive"))
      (node (ref "U8") (pin "11") (pinfunction "LED_NO.9_11") (pintype "passive"))
    )
    (net (code "47") (name "Net-(D3C-3_CATHODE)") (class "Default")
      (node (ref "D3") (pin "18") (pinfunction "3_CATHODE_18") (pintype "passive"))
      (node (ref "U8") (pin "12") (pinfunction "LED_NO.8_12") (pintype "passive"))
    )
    (net (code "48") (name "Net-(D3D-4_CATHODE)") (class "Default")
      (node (ref "D3") (pin "17") (pinfunction "4_CATHODE_17") (pintype "passive"))
      (node (ref "U8") (pin "13") (pinfunction "LED_NO.7_13") (pintype "passive"))
    )
    (net (code "49") (name "Net-(D3E-5_CATHODE)") (class "Default")
      (node (ref "D3") (pin "16") (pinfunction "5_CATHODE_16") (pintype "passive"))
      (node (ref "U8") (pin "14") (pinfunction "LED_NO.6_14") (pintype "passive"))
    )
    (net (code "50") (name "Net-(D3F-6_CATHODE)") (class "Default")
      (node (ref "D3") (pin "15") (pinfunction "6_CATHODE_15") (pintype "passive"))
      (node (ref "U8") (pin "15") (pinfunction "LED_NO.5_15") (pintype "passive"))
    )
    (net (code "51") (name "Net-(D3G-7_CATHODE)") (class "Default")
      (node (ref "D3") (pin "14") (pinfunction "7_CATHODE_14") (pintype "passive"))
      (node (ref "U8") (pin "16") (pinfunction "LED_NO.4_16") (pintype "passive"))
    )
    (net (code "52") (name "Net-(D3H-8_CATHODE)") (class "Default")
      (node (ref "D3") (pin "13") (pinfunction "8_CATHODE_13") (pintype "passive"))
      (node (ref "U8") (pin "17") (pinfunction "LED_NO.3_17") (pintype "passive"))
    )
    (net (code "53") (name "Net-(D3I-9_CATHODE)") (class "Default")
      (node (ref "D3") (pin "12") (pinfunction "9_CATHODE_12") (pintype "passive"))
      (node (ref "U8") (pin "18") (pinfunction "LED_NO.2_18") (pintype "passive"))
    )
    (net (code "54") (name "Net-(D3J-10_CATHODE)") (class "Default")
      (node (ref "D3") (pin "11") (pinfunction "10_CATHODE_11") (pintype "passive"))
      (node (ref "U8") (pin "1") (pinfunction "LED_NO.1_1") (pintype "passive"))
    )
    (net (code "55") (name "Net-(J1-Vin)") (class "Default")
      (node (ref "C1") (pin "1") (pinfunction "1_1") (pintype "passive"))
      (node (ref "J1") (pin "1") (pinfunction "Vin_1") (pintype "passive"))
      (node (ref "U9") (pin "1") (pinfunction "IN_1") (pintype "input"))
    )
    (net (code "56") (name "Net-(SD1-a)") (class "Default")
      (node (ref "R3") (pin "2") (pinfunction "2_2") (pintype "passive"))
      (node (ref "SD1") (pin "2") (pinfunction "a_2") (pintype "passive"))
    )
    (net (code "57") (name "Net-(SD1-b)") (class "Default")
      (node (ref "R1") (pin "2") (pinfunction "2_2") (pintype "passive"))
      (node (ref "SD1") (pin "1") (pinfunction "b_1") (pintype "passive"))
    )
    (net (code "58") (name "Net-(SD1-c)") (class "Default")
      (node (ref "R11") (pin "2") (pinfunction "2_2") (pintype "passive"))
      (node (ref "SD1") (pin "9") (pinfunction "c_9") (pintype "passive"))
    )
    (net (code "59") (name "Net-(SD1-d)") (class "Default")
      (node (ref "R13") (pin "2") (pinfunction "2_2") (pintype "passive"))
      (node (ref "SD1") (pin "7") (pinfunction "d_7") (pintype "passive"))
    )
    (net (code "60") (name "Net-(SD1-e)") (class "Default")
      (node (ref "R9") (pin "2") (pinfunction "2_2") (pintype "passive"))
      (node (ref "SD1") (pin "6") (pinfunction "e_6") (pintype "passive"))
    )
    (net (code "61") (name "Net-(SD1-f)") (class "Default")
      (node (ref "R5") (pin "2") (pinfunction "2_2") (pintype "passive"))
      (node (ref "SD1") (pin "4") (pinfunction "f_4") (pintype "passive"))
    )
    (net (code "62") (name "Net-(SD1-g)") (class "Default")
      (node (ref "R7") (pin "2") (pinfunction "2_2") (pintype "passive"))
      (node (ref "SD1") (pin "5") (pinfunction "g_5") (pintype "passive"))
    )
    (net (code "63") (name "Net-(SD2-a)") (class "Default")
      (node (ref "R6") (pin "1") (pinfunction "1_1") (pintype "passive"))
      (node (ref "SD2") (pin "2") (pinfunction "a_2") (pintype "passive"))
    )
    (net (code "64") (name "Net-(SD2-b)") (class "Default")
      (node (ref "R8") (pin "1") (pinfunction "1_1") (pintype "passive"))
      (node (ref "SD2") (pin "1") (pinfunction "b_1") (pintype "passive"))
    )
    (net (code "65") (name "Net-(SD2-c)") (class "Default")
      (node (ref "R10") (pin "1") (pinfunction "1_1") (pintype "passive"))
      (node (ref "SD2") (pin "9") (pinfunction "c_9") (pintype "passive"))
    )
    (net (code "66") (name "Net-(SD2-d)") (class "Default")
      (node (ref "R14") (pin "1") (pinfunction "1_1") (pintype "passive"))
      (node (ref "SD2") (pin "7") (pinfunction "d_7") (pintype "passive"))
    )
    (net (code "67") (name "Net-(SD2-e)") (class "Default")
      (node (ref "R12") (pin "1") (pinfunction "1_1") (pintype "passive"))
      (node (ref "SD2") (pin "6") (pinfunction "e_6") (pintype "passive"))
    )
    (net (code "68") (name "Net-(SD2-f)") (class "Default")
      (node (ref "R4") (pin "1") (pinfunction "1_1") (pintype "passive"))
      (node (ref "SD2") (pin "4") (pinfunction "f_4") (pintype "passive"))
    )
    (net (code "69") (name "Net-(SD2-g)") (class "Default")
      (node (ref "R2") (pin "1") (pinfunction "1_1") (pintype "passive"))
      (node (ref "SD2") (pin "5") (pinfunction "g_5") (pintype "passive"))
    )
    (net (code "70") (name "Net-(U1-A)") (class "Default")
      (node (ref "RP4") (pin "6") (pinfunction "6_6") (pintype "passive"))
      (node (ref "U1") (pin "7") (pinfunction "A_7") (pintype "input"))
      (node (ref "U6") (pin "4") (pinfunction "QE_4") (pintype "tri_state"))
    )
    (net (code "71") (name "Net-(U1-B)") (class "Default")
      (node (ref "RP4") (pin "7") (pinfunction "7_7") (pintype "passive"))
      (node (ref "U1") (pin "1") (pinfunction "B_1") (pintype "input"))
      (node (ref "U6") (pin "5") (pinfunction "QF_5") (pintype "tri_state"))
    )
    (net (code "72") (name "Net-(U1-C)") (class "Default")
      (node (ref "RP4") (pin "8") (pinfunction "8_8") (pintype "passive"))
      (node (ref "U1") (pin "2") (pinfunction "C_2") (pintype "input"))
      (node (ref "U6") (pin "6") (pinfunction "QG_6") (pintype "tri_state"))
    )
    (net (code "73") (name "Net-(U1-D)") (class "Default")
      (node (ref "RP4") (pin "9") (pinfunction "9_9") (pintype "passive"))
      (node (ref "U1") (pin "6") (pinfunction "D_6") (pintype "input"))
      (node (ref "U6") (pin "7") (pinfunction "QH_7") (pintype "tri_state"))
    )
    (net (code "74") (name "Net-(U1-~{a})") (class "Default")
      (node (ref "R3") (pin "1") (pinfunction "1_1") (pintype "passive"))
      (node (ref "U1") (pin "13") (pinfunction "~{a}_13") (pintype "open_collector"))
    )
    (net (code "75") (name "Net-(U1-~{b})") (class "Default")
      (node (ref "R1") (pin "1") (pinfunction "1_1") (pintype "passive"))
      (node (ref "U1") (pin "12") (pinfunction "~{b}_12") (pintype "open_collector"))
    )
    (net (code "76") (name "Net-(U1-~{c})") (class "Default")
      (node (ref "R11") (pin "1") (pinfunction "1_1") (pintype "passive"))
      (node (ref "U1") (pin "11") (pinfunction "~{c}_11") (pintype "open_collector"))
    )
    (net (code "77") (name "Net-(U1-~{d})") (class "Default")
      (node (ref "R13") (pin "1") (pinfunction "1_1") (pintype "passive"))
      (node (ref "U1") (pin "10") (pinfunction "~{d}_10") (pintype "open_collector"))
    )
    (net (code "78") (name "Net-(U1-~{e})") (class "Default")
      (node (ref "R9") (pin "1") (pinfunction "1_1") (pintype "passive"))
      (node (ref "U1") (pin "9") (pinfunction "~{e}_9") (pintype "open_collector"))
    )
    (net (code "79") (name "Net-(U1-~{f})") (class "Default")
      (node (ref "R5") (pin "1") (pinfunction "1_1") (pintype "passive"))
      (node (ref "U1") (pin "15") (pinfunction "~{f}_15") (pintype "open_collector"))
    )
    (net (code "80") (name "Net-(U1-~{g})") (class "Default")
      (node (ref "R7") (pin "1") (pinfunction "1_1") (pintype "passive"))
      (node (ref "U1") (pin "14") (pinfunction "~{g}_14") (pintype "open_collector"))
    )
    (net (code "81") (name "Net-(U2-A)") (class "Default")
      (node (ref "RP4") (pin "2") (pinfunction "2_2") (pintype "passive"))
      (node (ref "U2") (pin "7") (pinfunction "A_7") (pintype "input"))
      (node (ref "U6") (pin "15") (pinfunction "QA_15") (pintype "tri_state"))
    )
    (net (code "82") (name "Net-(U2-B)") (class "Default")
      (node (ref "RP4") (pin "3") (pinfunction "3_3") (pintype "passive"))
      (node (ref "U2") (pin "1") (pinfunction "B_1") (pintype "input"))
      (node (ref "U6") (pin "1") (pinfunction "QB_1") (pintype "tri_state"))
    )
    (net (code "83") (name "Net-(U2-C)") (class "Default")
      (node (ref "RP4") (pin "4") (pinfunction "4_4") (pintype "passive"))
      (node (ref "U2") (pin "2") (pinfunction "C_2") (pintype "input"))
      (node (ref "U6") (pin "2") (pinfunction "QC_2") (pintype "tri_state"))
    )
    (net (code "84") (name "Net-(U2-D)") (class "Default")
      (node (ref "RP4") (pin "5") (pinfunction "5_5") (pintype "passive"))
      (node (ref "U2") (pin "6") (pinfunction "D_6") (pintype "input"))
      (node (ref "U6") (pin "3") (pinfunction "QD_3") (pintype "tri_state"))
    )
    (net (code "85") (name "Net-(U2-~{a})") (class "Default")
      (node (ref "R6") (pin "2") (pinfunction "2_2") (pintype "passive"))
      (node (ref "U2") (pin "13") (pinfunction "~{a}_13") (pintype "open_collector"))
    )
    (net (code "86") (name "Net-(U2-~{b})") (class "Default")
      (node (ref "R8") (pin "2") (pinfunction "2_2") (pintype "passive"))
      (node (ref "U2") (pin "12") (pinfunction "~{b}_12") (pintype "open_collector"))
    )
    (net (code "87") (name "Net-(U2-~{c})") (class "Default")
      (node (ref "R10") (pin "2") (pinfunction "2_2") (pintype "passive"))
      (node (ref "U2") (pin "11") (pinfunction "~{c}_11") (pintype "open_collector"))
    )
    (net (code "88") (name "Net-(U2-~{d})") (class "Default")
      (node (ref "R14") (pin "2") (pinfunction "2_2") (pintype "passive"))
      (node (ref "U2") (pin "10") (pinfunction "~{d}_10") (pintype "open_collector"))
    )
    (net (code "89") (name "Net-(U2-~{e})") (class "Default")
      (node (ref "R12") (pin "2") (pinfunction "2_2") (pintype "passive"))
      (node (ref "U2") (pin "9") (pinfunction "~{e}_9") (pintype "open_collector"))
    )
    (net (code "90") (name "Net-(U2-~{f})") (class "Default")
      (node (ref "R4") (pin "2") (pinfunction "2_2") (pintype "passive"))
      (node (ref "U2") (pin "15") (pinfunction "~{f}_15") (pintype "open_collector"))
    )
    (net (code "91") (name "Net-(U2-~{g})") (class "Default")
      (node (ref "R2") (pin "2") (pinfunction "2_2") (pintype "passive"))
      (node (ref "U2") (pin "14") (pinfunction "~{g}_14") (pintype "open_collector"))
    )
    (net (code "92") (name "Net-(U7-PB6_(PCINT6{slash}XTAL1{slash}TOSC1))") (class "Default")
      (node (ref "C4") (pin "2") (pinfunction "2_2") (pintype "passive"))
      (node (ref "U7") (pin "9") (pinfunction "PB6_(PCINT6/XTAL1/TOSC1)_9") (pintype "bidirectional"))
      (node (ref "X1") (pin "1") (pinfunction "1_1") (pintype "passive"))
    )
    (net (code "93") (name "Net-(U7-PB7_(PCINT7{slash}XTAL2{slash}TOSC2))") (class "Default")
      (node (ref "C3") (pin "2") (pinfunction "2_2") (pintype "passive"))
      (node (ref "U7") (pin "10") (pinfunction "PB7_(PCINT7/XTAL2/TOSC2)_10") (pintype "bidirectional"))
      (node (ref "X1") (pin "2") (pinfunction "2_2") (pintype "passive"))
    )
    (net (code "94") (name "Net-(U8-DIVIDER(HIGH_END))") (class "Default")
      (node (ref "R18") (pin "2") (pinfunction "2_2") (pintype "passive"))
      (node (ref "U8") (pin "6") (pinfunction "DIVIDER(HIGH_END)_6") (pintype "passive"))
      (node (ref "U8") (pin "7") (pinfunction "REFERENCE_OUTPUT_7") (pintype "passive"))
    )
    (net (code "95") (name "Net-(U8-REFERENCE_ADJUST)") (class "Default")
      (node (ref "R17") (pin "1") (pinfunction "1_1") (pintype "passive"))
      (node (ref "R18") (pin "1") (pinfunction "1_1") (pintype "passive"))
      (node (ref "U8") (pin "8") (pinfunction "REFERENCE_ADJUST_8") (pintype "passive"))
    )
    (net (code "96") (name "Net-(U8-SIGNAL_INPUT)") (class "Default")
      (node (ref "C5") (pin "2") (pinfunction "2_2") (pintype "passive"))
      (node (ref "R19") (pin "2") (pinfunction "2_2") (pintype "passive"))
      (node (ref "U8") (pin "5") (pinfunction "SIGNAL_INPUT_5") (pintype "passive"))
    )
    (net (code "97") (name "VCC") (class "Default")
      (node (ref "BLK1") (pin "5") (pinfunction "VCC_5") (pintype "passive"))
      (node (ref "BLK2") (pin "5") (pinfunction "VCC_5") (pintype "passive"))
      (node (ref "BLK3") (pin "5") (pinfunction "VCC_5") (pintype "passive"))
      (node (ref "C2") (pin "1") (pinfunction "1_1") (pintype "passive"))
      (node (ref "D3") (pin "1") (pinfunction "1_ANODE_1") (pintype "passive"))
      (node (ref "D3") (pin "10") (pinfunction "10_ANODE_10") (pintype "passive"))
      (node (ref "D3") (pin "2") (pinfunction "2_ANODE_2") (pintype "passive"))
      (node (ref "D3") (pin "3") (pinfunction "3_ANODE_3") (pintype "passive"))
      (node (ref "D3") (pin "4") (pinfunction "4_ANODE_4") (pintype "passive"))
      (node (ref "D3") (pin "5") (pinfunction "5_ANODE_5") (pintype "passive"))
      (node (ref "D3") (pin "6") (pinfunction "6_ANODE_6") (pintype "passive"))
      (node (ref "D3") (pin "7") (pinfunction "7_ANODE_7") (pintype "passive"))
      (node (ref "D3") (pin "8") (pinfunction "8_ANODE_8") (pintype "passive"))
      (node (ref "D3") (pin "9") (pinfunction "9_ANODE_9") (pintype "passive"))
      (node (ref "SD1") (pin "3") (pinfunction "vcc_3") (pintype "passive"))
      (node (ref "SD1") (pin "8") (pinfunction "vcc_8") (pintype "passive"))
      (node (ref "SD2") (pin "3") (pinfunction "vcc_3") (pintype "passive"))
      (node (ref "SD2") (pin "8") (pinfunction "vcc_8") (pintype "passive"))
      (node (ref "U1") (pin "16") (pinfunction "VCC_16") (pintype "power_in"))
      (node (ref "U1") (pin "3") (pinfunction "~{LT}_3") (pintype "input"))
      (node (ref "U1") (pin "5") (pinfunction "~{RBI}_5") (pintype "input"))
      (node (ref "U2") (pin "16") (pinfunction "VCC_16") (pintype "power_in"))
      (node (ref "U2") (pin "3") (pinfunction "~{LT}_3") (pintype "input"))
      (node (ref "U2") (pin "5") (pinfunction "~{RBI}_5") (pintype "input"))
      (node (ref "U3") (pin "16") (pinfunction "VCC_16") (pintype "power_in"))
      (node (ref "U4") (pin "16") (pinfunction "VCC_16") (pintype "power_in"))
      (node (ref "U5") (pin "16") (pinfunction "VCC_16") (pintype "power_in"))
      (node (ref "U6") (pin "10") (pinfunction "~{SRCLR}_10") (pintype "input"))
      (node (ref "U6") (pin "16") (pinfunction "VCC_16") (pintype "power_in"))
      (node (ref "U7") (pin "20") (pinfunction "AVCC_20") (pintype "power_in"))
      (node (ref "U7") (pin "21") (pinfunction "AREF_21") (pintype "power_in"))
      (node (ref "U7") (pin "7") (pinfunction "VCC_7") (pintype "power_in"))
      (node (ref "U8") (pin "3") (pinfunction "V+_3") (pintype "power_in"))
      (node (ref "U8") (pin "9") (pinfunction "MODE_SELECT_9") (pintype "input"))
      (node (ref "U9") (pin "3") (pinfunction "OUT_3") (pintype "passive"))
    )
    (net (code "98") (name "unconnected-(PTH1-Pad1)") (class "Default")
      (node (ref "PTH1") (pin "1") (pinfunction "1_1") (pintype "passive"))
    )
    (net (code "99") (name "unconnected-(PTH2-Pad1)") (class "Default")
      (node (ref "PTH2") (pin "1") (pinfunction "1_1") (pintype "passive"))
    )
    (net (code "100") (name "unconnected-(PTH3-Pad1)") (class "Default")
      (node (ref "PTH3") (pin "1") (pinfunction "1_1") (pintype "passive"))
    )
    (net (code "101") (name "unconnected-(PTH4-Pad1)") (class "Default")
      (node (ref "PTH4") (pin "1") (pinfunction "1_1") (pintype "passive"))
    )
    (net (code "102") (name "unconnected-(RP1-Pad1)") (class "Default")
      (node (ref "RP1") (pin "1") (pinfunction "1_1") (pintype "passive"))
    )
    (net (code "103") (name "unconnected-(RP1-Pad2)") (class "Default")
      (node (ref "RP1") (pin "2") (pinfunction "2_2") (pintype "passive"))
    )
    (net (code "104") (name "unconnected-(RP1-Pad3)") (class "Default")
      (node (ref "RP1") (pin "3") (pinfunction "3_3") (pintype "passive"))
    )
    (net (code "105") (name "unconnected-(RP1-Pad4)") (class "Default")
      (node (ref "RP1") (pin "4") (pinfunction "4_4") (pintype "passive"))
    )
    (net (code "106") (name "unconnected-(RP1-Pad5)") (class "Default")
      (node (ref "RP1") (pin "5") (pinfunction "5_5") (pintype "passive"))
    )
    (net (code "107") (name "unconnected-(RP1-Pad6)") (class "Default")
      (node (ref "RP1") (pin "6") (pinfunction "6_6") (pintype "passive"))
    )
    (net (code "108") (name "unconnected-(RP1-Pad7)") (class "Default")
      (node (ref "RP1") (pin "7") (pinfunction "7_7") (pintype "passive"))
    )
    (net (code "109") (name "unconnected-(RP1-Pad8)") (class "Default")
      (node (ref "RP1") (pin "8") (pinfunction "8_8") (pintype "passive"))
    )
    (net (code "110") (name "unconnected-(RP1-Pad9)") (class "Default")
      (node (ref "RP1") (pin "9") (pinfunction "9_9") (pintype "passive"))
    )
    (net (code "111") (name "unconnected-(RP2-Pad1)") (class "Default")
      (node (ref "RP2") (pin "1") (pinfunction "1_1") (pintype "passive"))
    )
    (net (code "112") (name "unconnected-(RP2-Pad2)") (class "Default")
      (node (ref "RP2") (pin "2") (pinfunction "2_2") (pintype "passive"))
    )
    (net (code "113") (name "unconnected-(RP2-Pad3)") (class "Default")
      (node (ref "RP2") (pin "3") (pinfunction "3_3") (pintype "passive"))
    )
    (net (code "114") (name "unconnected-(RP2-Pad4)") (class "Default")
      (node (ref "RP2") (pin "4") (pinfunction "4_4") (pintype "passive"))
    )
    (net (code "115") (name "unconnected-(RP2-Pad5)") (class "Default")
      (node (ref "RP2") (pin "5") (pinfunction "5_5") (pintype "passive"))
    )
    (net (code "116") (name "unconnected-(RP2-Pad6)") (class "Default")
      (node (ref "RP2") (pin "6") (pinfunction "6_6") (pintype "passive"))
    )
    (net (code "117") (name "unconnected-(RP2-Pad7)") (class "Default")
      (node (ref "RP2") (pin "7") (pinfunction "7_7") (pintype "passive"))
    )
    (net (code "118") (name "unconnected-(RP2-Pad8)") (class "Default")
      (node (ref "RP2") (pin "8") (pinfunction "8_8") (pintype "passive"))
    )
    (net (code "119") (name "unconnected-(RP2-Pad9)") (class "Default")
      (node (ref "RP2") (pin "9") (pinfunction "9_9") (pintype "passive"))
    )
    (net (code "120") (name "unconnected-(RP3-Pad1)") (class "Default")
      (node (ref "RP3") (pin "1") (pinfunction "1_1") (pintype "passive"))
    )
    (net (code "121") (name "unconnected-(RP3-Pad2)") (class "Default")
      (node (ref "RP3") (pin "2") (pinfunction "2_2") (pintype "passive"))
    )
    (net (code "122") (name "unconnected-(RP3-Pad3)") (class "Default")
      (node (ref "RP3") (pin "3") (pinfunction "3_3") (pintype "passive"))
    )
    (net (code "123") (name "unconnected-(RP3-Pad4)") (class "Default")
      (node (ref "RP3") (pin "4") (pinfunction "4_4") (pintype "passive"))
    )
    (net (code "124") (name "unconnected-(RP3-Pad5)") (class "Default")
      (node (ref "RP3") (pin "5") (pinfunction "5_5") (pintype "passive"))
    )
    (net (code "125") (name "unconnected-(RP3-Pad6)") (class "Default")
      (node (ref "RP3") (pin "6") (pinfunction "6_6") (pintype "passive"))
    )
    (net (code "126") (name "unconnected-(RP3-Pad7)") (class "Default")
      (node (ref "RP3") (pin "7") (pinfunction "7_7") (pintype "passive"))
    )
    (net (code "127") (name "unconnected-(RP3-Pad8)") (class "Default")
      (node (ref "RP3") (pin "8") (pinfunction "8_8") (pintype "passive"))
    )
    (net (code "128") (name "unconnected-(RP3-Pad9)") (class "Default")
      (node (ref "RP3") (pin "9") (pinfunction "9_9") (pintype "passive"))
    )
    (net (code "129") (name "unconnected-(SD1-dp-Pad10)") (class "Default")
      (node (ref "SD1") (pin "10") (pinfunction "dp_10") (pintype "passive"))
    )
    (net (code "130") (name "unconnected-(SD2-dp-Pad10)") (class "Default")
      (node (ref "SD2") (pin "10") (pinfunction "dp_10") (pintype "passive"))
    )
    (net (code "131") (name "unconnected-(SW1-Pad2)") (class "Default")
      (node (ref "SW1") (pin "2") (pinfunction "2_2") (pintype "passive"))
    )
    (net (code "132") (name "unconnected-(SW1-Pad4)") (class "Default")
      (node (ref "SW1") (pin "4") (pinfunction "4_4") (pintype "passive"))
    )
    (net (code "133") (name "unconnected-(SW2-Pad2)") (class "Default")
      (node (ref "SW2") (pin "2") (pinfunction "2_2") (pintype "passive"))
    )
    (net (code "134") (name "unconnected-(SW2-Pad4)") (class "Default")
      (node (ref "SW2") (pin "4") (pinfunction "4_4") (pintype "passive"))
    )
    (net (code "135") (name "unconnected-(U3-QH-Pad9)") (class "Default")
      (node (ref "U3") (pin "9") (pinfunction "QH_9") (pintype "output"))
    )
    (net (code "136") (name "unconnected-(U4-QH-Pad9)") (class "Default")
      (node (ref "U4") (pin "9") (pinfunction "QH_9") (pintype "output"))
    )
    (net (code "137") (name "unconnected-(U5-QH-Pad9)") (class "Default")
      (node (ref "U5") (pin "9") (pinfunction "QH_9") (pintype "output"))
    )
    (net (code "138") (name "unconnected-(U6-QH'-Pad9)") (class "Default")
      (node (ref "U6") (pin "9") (pinfunction "QH'_9") (pintype "output"))
    )
    (net (code "139") (name "unconnected-(U7-PB5_(SCK{slash}PCINT5)-Pad19)") (class "Default")
      (node (ref "U7") (pin "19") (pinfunction "PB5_(SCK/PCINT5)_19") (pintype "bidirectional"))
    )
    (net (code "140") (name "unconnected-(U7-PC0_(ADC0{slash}PCINT8)-Pad23)") (class "Default")
      (node (ref "U7") (pin "23") (pinfunction "PC0_(ADC0/PCINT8)_23") (pintype "bidirectional"))
    )
    (net (code "141") (name "unconnected-(U7-PC4_(ADC4{slash}SDA{slash}PCINT12)-Pad27)") (class "Default")
      (node (ref "U7") (pin "27") (pinfunction "PC4_(ADC4/SDA/PCINT12)_27") (pintype "bidirectional"))
    )
    (net (code "142") (name "unconnected-(U7-PC5_(ADC5{slash}SCL{slash}PCINT13)-Pad28)") (class "Default")
      (node (ref "U7") (pin "28") (pinfunction "PC5_(ADC5/SCL/PCINT13)_28") (pintype "bidirectional"))
    )
    (net (code "143") (name "unconnected-(U7-PC6_(PCINT14{slash}~{RESET})-Pad1)") (class "Default")
      (node (ref "U7") (pin "1") (pinfunction "PC6_(PCINT14/~{RESET})_1") (pintype "bidirectional"))
    )
    (net (code "144") (name "unconnected-(U7-PD0_(PCINT16{slash}RXD)-Pad2)") (class "Default")
      (node (ref "U7") (pin "2") (pinfunction "PD0_(PCINT16/RXD)_2") (pintype "bidirectional"))
    )
    (net (code "145") (name "unconnected-(U7-PD1_(PCINT17{slash}TXD)-Pad3)") (class "Default")
      (node (ref "U7") (pin "3") (pinfunction "PD1_(PCINT17/TXD)_3") (pintype "bidirectional"))
    )
    (net (code "146") (name "unconnected-(U7-PD6_(PCINT22{slash}OC0A{slash}AIN0)-Pad12)") (class "Default")
      (node (ref "U7") (pin "12") (pinfunction "PD6_(PCINT22/OC0A/AIN0)_12") (pintype "bidirectional"))
    )
  )
)
